# PowerBoard.net
KiCad netlist of a schematic drawn in Altium Designer
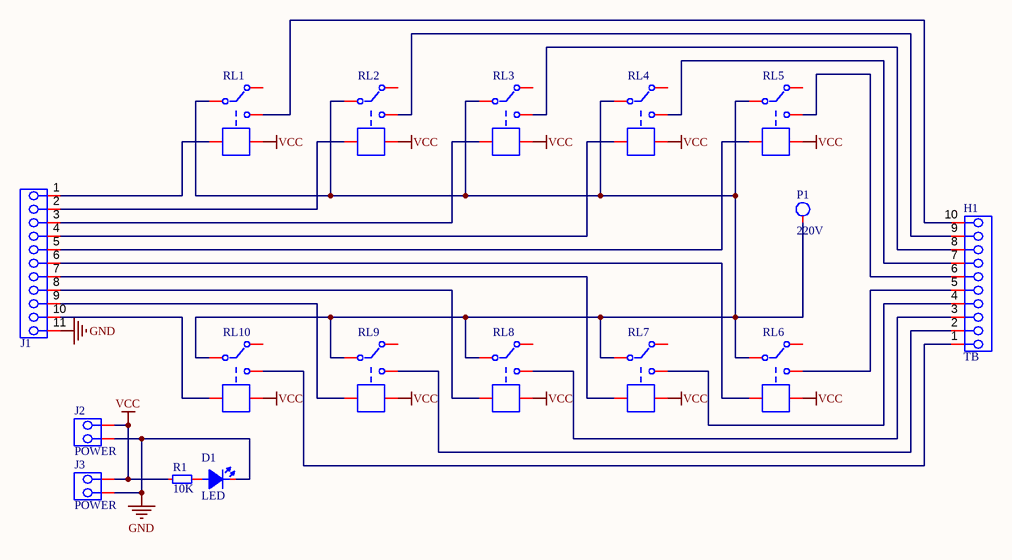
[diagram p0: PowerBoard.SchDoc]

(export (version "E")
  (design (tool "Eeschema 10.0.6"))
  (components
    (comp (ref "D1") (value "LED") (footprint "LED_5MM") (libsource (lib "MyAltiumLibrary") (part "LED 5MM")))
    (comp (ref "H1")
      (value "TB")
      (footprint "TERMINAL-BLOCK-7.62MM -10PIN")
      (libsource (lib "MyAltiumLibrary") (part "TERMINAL-BLOCK-7.62MM-10PIN"))
    )
    (comp (ref "J1")
      (value "HEADER-MALE-2.54MM")
      (footprint "HEADER-MALE-11PINS-2.54MM")
      (libsource (lib "MyAltiumLibrary") (part "HEADER-MALE-11PINS-2.54MM"))
    )
    (comp (ref "J2")
      (value "POWER")
      (footprint "DG306-5.0-02P-12-00AH")
      (libsource (lib "MyAltiumLibrary") (part "DG306-5.0-02P-12-00AH"))
    )
    (comp (ref "J3")
      (value "POWER")
      (footprint "DG306-5.0-02P-12-00AH")
      (libsource (lib "MyAltiumLibrary") (part "DG306-5.0-02P-12-00AH"))
    )
    (comp (ref "P1")
      (value "220V")
      (footprint "SolderPoint")
      (libsource (lib "MyAltiumLibrary") (part "SolderPoint"))
    )
    (comp (ref "R1")
      (value "10K")
      (footprint "RES-0.25W-H")
      (libsource (lib "MyAltiumLibrary") (part "Resistors THD"))
    )
    (comp (ref "RL1")
      (value "Relay-SONGLE-SRD-05VDC")
      (footprint "RELAY-SONGLE-SRD-05VDC_BLUE")
      (libsource (lib "MyAltiumLibrary") (part "Relay-SONGLE-SRD-05VDC"))
    )
    (comp (ref "RL2")
      (value "Relay-SONGLE-SRD-05VDC")
      (footprint "RELAY-SONGLE-SRD-05VDC_BLUE")
      (libsource (lib "MyAltiumLibrary") (part "Relay-SONGLE-SRD-05VDC"))
    )
    (comp (ref "RL3")
      (value "Relay-SONGLE-SRD-05VDC")
      (footprint "RELAY-SONGLE-SRD-05VDC_BLUE")
      (libsource (lib "MyAltiumLibrary") (part "Relay-SONGLE-SRD-05VDC"))
    )
    (comp (ref "RL4")
      (value "Relay-SONGLE-SRD-05VDC")
      (footprint "RELAY-SONGLE-SRD-05VDC_BLUE")
      (libsource (lib "MyAltiumLibrary") (part "Relay-SONGLE-SRD-05VDC"))
    )
    (comp (ref "RL5")
      (value "Relay-SONGLE-SRD-05VDC")
      (footprint "RELAY-SONGLE-SRD-05VDC_BLUE")
      (libsource (lib "MyAltiumLibrary") (part "Relay-SONGLE-SRD-05VDC"))
    )
    (comp (ref "RL6")
      (value "Relay-SONGLE-SRD-05VDC")
      (footprint "RELAY-SONGLE-SRD-05VDC_BLUE")
      (libsource (lib "MyAltiumLibrary") (part "Relay-SONGLE-SRD-05VDC"))
    )
    (comp (ref "RL7")
      (value "Relay-SONGLE-SRD-05VDC")
      (footprint "RELAY-SONGLE-SRD-05VDC_BLUE")
      (libsource (lib "MyAltiumLibrary") (part "Relay-SONGLE-SRD-05VDC"))
    )
    (comp (ref "RL8")
      (value "Relay-SONGLE-SRD-05VDC")
      (footprint "RELAY-SONGLE-SRD-05VDC_BLUE")
      (libsource (lib "MyAltiumLibrary") (part "Relay-SONGLE-SRD-05VDC"))
    )
    (comp (ref "RL9")
      (value "Relay-SONGLE-SRD-05VDC")
      (footprint "RELAY-SONGLE-SRD-05VDC_BLUE")
      (libsource (lib "MyAltiumLibrary") (part "Relay-SONGLE-SRD-05VDC"))
    )
    (comp (ref "RL10")
      (value "Relay-SONGLE-SRD-05VDC")
      (footprint "RELAY-SONGLE-SRD-05VDC_BLUE")
      (libsource (lib "MyAltiumLibrary") (part "Relay-SONGLE-SRD-05VDC"))
    )
  )
  (nets
    (net (code "1") (name "GND") (class "Default")
      (node (ref "D1") (pin "2") (pinfunction "K_2") (pintype "passive"))
      (node (ref "J1") (pin "11") (pinfunction "11_11") (pintype "passive"))
      (node (ref "J2") (pin "2") (pinfunction "2_2") (pintype "passive"))
      (node (ref "J3") (pin "2") (pinfunction "2_2") (pintype "passive"))
    )
    (net (code "2") (name "Net-(D1-A)") (class "Default")
      (node (ref "D1") (pin "1") (pinfunction "A_1") (pintype "passive"))
      (node (ref "R1") (pin "2") (pinfunction "2_2") (pintype "passive"))
    )
    (net (code "3") (name "Net-(H1-Pad1)") (class "Default")
      (node (ref "H1") (pin "1") (pinfunction "1_1") (pintype "passive"))
      (node (ref "RL10") (pin "4") (pinfunction "4_4") (pintype "passive"))
    )
    (net (code "4") (name "Net-(H1-Pad2)") (class "Default")
      (node (ref "H1") (pin "2") (pinfunction "2_2") (pintype "passive"))
      (node (ref "RL9") (pin "4") (pinfunction "4_4") (pintype "passive"))
    )
    (net (code "5") (name "Net-(H1-Pad3)") (class "Default")
      (node (ref "H1") (pin "3") (pinfunction "3_3") (pintype "passive"))
      (node (ref "RL8") (pin "4") (pinfunction "4_4") (pintype "passive"))
    )
    (net (code "6") (name "Net-(H1-Pad4)") (class "Default")
      (node (ref "H1") (pin "4") (pinfunction "4_4") (pintype "passive"))
      (node (ref "RL7") (pin "4") (pinfunction "4_4") (pintype "passive"))
    )
    (net (code "7") (name "Net-(H1-Pad5)") (class "Default")
      (node (ref "H1") (pin "5") (pinfunction "5_5") (pintype "passive"))
      (node (ref "RL6") (pin "4") (pinfunction "4_4") (pintype "passive"))
    )
    (net (code "8") (name "Net-(H1-Pad6)") (class "Default")
      (node (ref "H1") (pin "6") (pinfunction "6_6") (pintype "passive"))
      (node (ref "RL5") (pin "4") (pinfunction "4_4") (pintype "passive"))
    )
    (net (code "9") (name "Net-(H1-Pad7)") (class "Default")
      (node (ref "H1") (pin "7") (pinfunction "7_7") (pintype "passive"))
      (node (ref "RL4") (pin "4") (pinfunction "4_4") (pintype "passive"))
    )
    (net (code "10") (name "Net-(H1-Pad8)") (class "Default")
      (node (ref "H1") (pin "8") (pinfunction "8_8") (pintype "passive"))
      (node (ref "RL3") (pin "4") (pinfunction "4_4") (pintype "passive"))
    )
    (net (code "11") (name "Net-(H1-Pad9)") (class "Default")
      (node (ref "H1") (pin "9") (pinfunction "9_9") (pintype "passive"))
      (node (ref "RL2") (pin "4") (pinfunction "4_4") (pintype "passive"))
    )
    (net (code "12") (name "Net-(H1-Pad10)") (class "Default")
      (node (ref "H1") (pin "10") (pinfunction "10_10") (pintype "passive"))
      (node (ref "RL1") (pin "4") (pinfunction "4_4") (pintype "passive"))
    )
    (net (code "13") (name "Net-(J1-Pad1)") (class "Default")
      (node (ref "J1") (pin "1") (pinfunction "1_1") (pintype "passive"))
      (node (ref "RL1") (pin "1") (pinfunction "1_1") (pintype "passive"))
    )
    (net (code "14") (name "Net-(J1-Pad2)") (class "Default")
      (node (ref "J1") (pin "2") (pinfunction "2_2") (pintype "passive"))
      (node (ref "RL2") (pin "1") (pinfunction "1_1") (pintype "passive"))
    )
    (net (code "15") (name "Net-(J1-Pad3)") (class "Default")
      (node (ref "J1") (pin "3") (pinfunction "3_3") (pintype "passive"))
      (node (ref "RL3") (pin "1") (pinfunction "1_1") (pintype "passive"))
    )
    (net (code "16") (name "Net-(J1-Pad4)") (class "Default")
      (node (ref "J1") (pin "4") (pinfunction "4_4") (pintype "passive"))
      (node (ref "RL4") (pin "1") (pinfunction "1_1") (pintype "passive"))
    )
    (net (code "17") (name "Net-(J1-Pad5)") (class "Default")
      (node (ref "J1") (pin "5") (pinfunction "5_5") (pintype "passive"))
      (node (ref "RL5") (pin "1") (pinfunction "1_1") (pintype "passive"))
    )
    (net (code "18") (name "Net-(J1-Pad6)") (class "Default")
      (node (ref "J1") (pin "6") (pinfunction "6_6") (pintype "passive"))
      (node (ref "RL6") (pin "1") (pinfunction "1_1") (pintype "passive"))
    )
    (net (code "19") (name "Net-(J1-Pad7)") (class "Default")
      (node (ref "J1") (pin "7") (pinfunction "7_7") (pintype "passive"))
      (node (ref "RL7") (pin "1") (pinfunction "1_1") (pintype "passive"))
    )
    (net (code "20") (name "Net-(J1-Pad8)") (class "Default")
      (node (ref "J1") (pin "8") (pinfunction "8_8") (pintype "passive"))
      (node (ref "RL8") (pin "1") (pinfunction "1_1") (pintype "passive"))
    )
    (net (code "21") (name "Net-(J1-Pad9)") (class "Default")
      (node (ref "J1") (pin "9") (pinfunction "9_9") (pintype "passive"))
      (node (ref "RL9") (pin "1") (pinfunction "1_1") (pintype "passive"))
    )
    (net (code "22") (name "Net-(J1-Pad10)") (class "Default")
      (node (ref "J1") (pin "10") (pinfunction "10_10") (pintype "passive"))
      (node (ref "RL10") (pin "1") (pinfunction "1_1") (pintype "passive"))
    )
    (net (code "23") (name "Net-(P1-Pad1)") (class "Default")
      (node (ref "P1") (pin "1") (pinfunction "1_1") (pintype "passive"))
      (node (ref "RL1") (pin "2") (pinfunction "2_2") (pintype "passive"))
      (node (ref "RL10") (pin "2") (pinfunction "2_2") (pintype "passive"))
      (node (ref "RL2") (pin "2") (pinfunction "2_2") (pintype "passive"))
      (node (ref "RL3") (pin "2") (pinfunction "2_2") (pintype "passive"))
      (node (ref "RL4") (pin "2") (pinfunction "2_2") (pintype "passive"))
      (node (ref "RL5") (pin "2") (pinfunction "2_2") (pintype "passive"))
      (node (ref "RL6") (pin "2") (pinfunction "2_2") (pintype "passive"))
      (node (ref "RL7") (pin "2") (pinfunction "2_2") (pintype "passive"))
      (node (ref "RL8") (pin "2") (pinfunction "2_2") (pintype "passive"))
      (node (ref "RL9") (pin "2") (pinfunction "2_2") (pintype "passive"))
    )
    (net (code "24") (name "VCC") (class "Default")
      (node (ref "J2") (pin "1") (pinfunction "1_1") (pintype "passive"))
      (node (ref "J3") (pin "1") (pinfunction "1_1") (pintype "passive"))
      (node (ref "R1") (pin "1") (pinfunction "1_1") (pintype "passive"))
      (node (ref "RL1") (pin "3") (pinfunction "3_3") (pintype "passive"))
      (node (ref "RL10") (pin "3") (pinfunction "3_3") (pintype "passive"))
      (node (ref "RL2") (pin "3") (pinfunction "3_3") (pintype "passive"))
      (node (ref "RL3") (pin "3") (pinfunction "3_3") (pintype "passive"))
      (node (ref "RL4") (pin "3") (pinfunction "3_3") (pintype "passive"))
      (node (ref "RL5") (pin "3") (pinfunction "3_3") (pintype "passive"))
      (node (ref "RL6") (pin "3") (pinfunction "3_3") (pintype "passive"))
      (node (ref "RL7") (pin "3") (pinfunction "3_3") (pintype "passive"))
      (node (ref "RL8") (pin "3") (pinfunction "3_3") (pintype "passive"))
      (node (ref "RL9") (pin "3") (pinfunction "3_3") (pintype "passive"))
    )
    (net (code "25") (name "unconnected-(RL1-Pad5)") (class "Default")
      (node (ref "RL1") (pin "5") (pinfunction "5_5") (pintype "passive"))
    )
    (net (code "26") (name "unconnected-(RL2-Pad5)") (class "Default")
      (node (ref "RL2") (pin "5") (pinfunction "5_5") (pintype "passive"))
    )
    (net (code "27") (name "unconnected-(RL3-Pad5)") (class "Default")
      (node (ref "RL3") (pin "5") (pinfunction "5_5") (pintype "passive"))
    )
    (net (code "28") (name "unconnected-(RL4-Pad5)") (class "Default")
      (node (ref "RL4") (pin "5") (pinfunction "5_5") (pintype "passive"))
    )
    (net (code "29") (name "unconnected-(RL5-Pad5)") (class "Default")
      (node (ref "RL5") (pin "5") (pinfunction "5_5") (pintype "passive"))
    )
    (net (code "30") (name "unconnected-(RL6-Pad5)") (class "Default")
      (node (ref "RL6") (pin "5") (pinfunction "5_5") (pintype "passive"))
    )
    (net (code "31") (name "unconnected-(RL7-Pad5)") (class "Default")
      (node (ref "RL7") (pin "5") (pinfunction "5_5") (pintype "passive"))
    )
    (net (code "32") (name "unconnected-(RL8-Pad5)") (class "Default")
      (node (ref "RL8") (pin "5") (pinfunction "5_5") (pintype "passive"))
    )
    (net (code "33") (name "unconnected-(RL9-Pad5)") (class "Default")
      (node (ref "RL9") (pin "5") (pinfunction "5_5") (pintype "passive"))
    )
    (net (code "34") (name "unconnected-(RL10-Pad5)") (class "Default")
      (node (ref "RL10") (pin "5") (pinfunction "5_5") (pintype "passive"))
    )
  )
)
